# Forward_Reverse_circuit.net
KiCad netlist of a schematic drawn in EAGLE
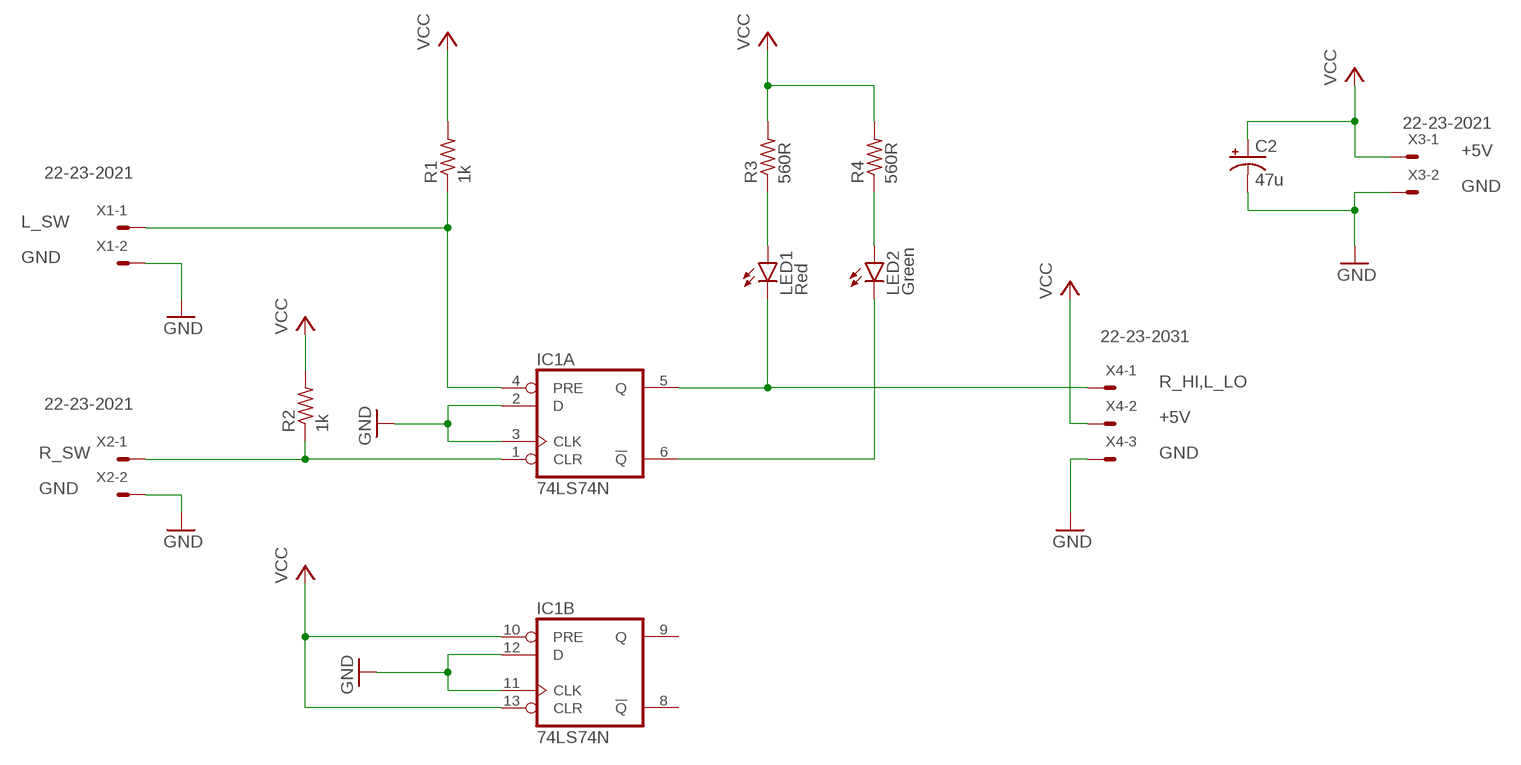
[diagram p0: schematic, sheet 1]

(export (version "E")
  (design (tool "Eeschema 10.0.6"))
  (components
    (comp (ref "C2")
      (value "47u")
      (footprint "eagle-import:E5-6")
      (libsource (lib "eagle-import") (part "CPOL-USE5-6"))
    )
    (comp (ref "IC1")
      (value "74LS74N")
      (footprint "eagle-import:DIL14")
      (libsource (lib "eagle-import") (part "7474NLS"))
    )
    (comp (ref "LED1")
      (value "Red")
      (footprint "eagle-import:LED5MM")
      (libsource (lib "eagle-import") (part "LED5MM"))
    )
    (comp (ref "LED2")
      (value "Green")
      (footprint "eagle-import:LED5MM")
      (libsource (lib "eagle-import") (part "LED5MM"))
    )
    (comp (ref "R1")
      (value "1k")
      (footprint "eagle-import:0207_12")
      (libsource (lib "eagle-import") (part "R-US_0207/12"))
    )
    (comp (ref "R2")
      (value "1k")
      (footprint "eagle-import:0207_12")
      (libsource (lib "eagle-import") (part "R-US_0207/12"))
    )
    (comp (ref "R3")
      (value "560R")
      (footprint "eagle-import:0207_12")
      (libsource (lib "eagle-import") (part "R-US_0207/12"))
    )
    (comp (ref "R4")
      (value "560R")
      (footprint "eagle-import:0207_12")
      (libsource (lib "eagle-import") (part "R-US_0207/12"))
    )
    (comp (ref "X1")
      (value "22-23-2021")
      (footprint "eagle-import:22-23-2021")
      (fields (field (name "MF") "MOLEX"))
      (libsource (lib "eagle-import") (part "22-23-2021"))
    )
    (comp (ref "X2")
      (value "22-23-2021")
      (footprint "eagle-import:22-23-2021")
      (fields (field (name "MF") "MOLEX"))
      (libsource (lib "eagle-import") (part "22-23-2021"))
    )
    (comp (ref "X3")
      (value "22-23-2021")
      (footprint "eagle-import:22-23-2021")
      (fields (field (name "MF") "MOLEX"))
      (libsource (lib "eagle-import") (part "22-23-2021"))
    )
    (comp (ref "X4")
      (value "22-23-2031")
      (footprint "eagle-import:22-23-2031")
      (fields (field (name "MF") "MOLEX"))
      (libsource (lib "eagle-import") (part "22-23-2031"))
    )
  )
  (nets
    (net (code "1") (name "/L_SW") (class "Default")
      (node (ref "IC1") (pin "4") (pinfunction "PRE_4") (pintype "input"))
      (node (ref "R1") (pin "1") (pinfunction "1_1") (pintype "passive"))
      (node (ref "X1") (pin "1") (pinfunction "S_1") (pintype "passive"))
    )
    (net (code "2") (name "/R_HI,L_LO") (class "Default")
      (node (ref "IC1") (pin "5") (pinfunction "Q_5") (pintype "output"))
      (node (ref "LED1") (pin "K") (pinfunction "C_K") (pintype "passive"))
      (node (ref "X4") (pin "1") (pinfunction "S_1") (pintype "passive"))
    )
    (net (code "3") (name "/R_SW") (class "Default")
      (node (ref "IC1") (pin "1") (pinfunction "CLR_1") (pintype "input"))
      (node (ref "R2") (pin "1") (pinfunction "1_1") (pintype "passive"))
      (node (ref "X2") (pin "1") (pinfunction "S_1") (pintype "passive"))
    )
    (net (code "4") (name "GND") (class "Default")
      (node (ref "C2") (pin "-") (pinfunction "-_-") (pintype "passive"))
      (node (ref "IC1") (pin "11") (pinfunction "CLK_11") (pintype "input"))
      (node (ref "IC1") (pin "12") (pinfunction "D_12") (pintype "input"))
      (node (ref "IC1") (pin "2") (pinfunction "D_2") (pintype "input"))
      (node (ref "IC1") (pin "3") (pinfunction "CLK_3") (pintype "input"))
      (node (ref "X1") (pin "2") (pinfunction "S_2") (pintype "passive"))
      (node (ref "X2") (pin "2") (pinfunction "S_2") (pintype "passive"))
      (node (ref "X3") (pin "2") (pinfunction "S_2") (pintype "passive"))
      (node (ref "X4") (pin "3") (pinfunction "S_3") (pintype "passive"))
    )
    (net (code "5") (name "Net-(IC1A-~{Q})") (class "Default")
      (node (ref "IC1") (pin "6") (pinfunction "~{Q}_6") (pintype "output"))
      (node (ref "LED2") (pin "K") (pinfunction "C_K") (pintype "passive"))
    )
    (net (code "6") (name "Net-(LED1-PadA)") (class "Default")
      (node (ref "LED1") (pin "A") (pinfunction "A_A") (pintype "passive"))
      (node (ref "R3") (pin "1") (pinfunction "1_1") (pintype "passive"))
    )
    (net (code "7") (name "Net-(LED2-PadA)") (class "Default")
      (node (ref "LED2") (pin "A") (pinfunction "A_A") (pintype "passive"))
      (node (ref "R4") (pin "1") (pinfunction "1_1") (pintype "passive"))
    )
    (net (code "8") (name "VCC") (class "Default")
      (node (ref "C2") (pin "+") (pinfunction "+_+") (pintype "passive"))
      (node (ref "IC1") (pin "10") (pinfunction "PRE_10") (pintype "input"))
      (node (ref "IC1") (pin "13") (pinfunction "CLR_13") (pintype "input"))
      (node (ref "R1") (pin "2") (pinfunction "2_2") (pintype "passive"))
      (node (ref "R2") (pin "2") (pinfunction "2_2") (pintype "passive"))
      (node (ref "R3") (pin "2") (pinfunction "2_2") (pintype "passive"))
      (node (ref "R4") (pin "2") (pinfunction "2_2") (pintype "passive"))
      (node (ref "X3") (pin "1") (pinfunction "S_1") (pintype "passive"))
      (node (ref "X4") (pin "2") (pinfunction "S_2") (pintype "passive"))
    )
    (net (code "9") (name "unconnected-(IC1B-Q-Pad9)") (class "Default")
      (node (ref "IC1") (pin "9") (pinfunction "Q_9") (pintype "output"))
    )
    (net (code "10") (name "unconnected-(IC1B-~{Q}-Pad8)") (class "Default")
      (node (ref "IC1") (pin "8") (pinfunction "~{Q}_8") (pintype "output"))
    )
  )
)
